# LabGener.net
KiCad netlist of a schematic drawn in Altium Designer
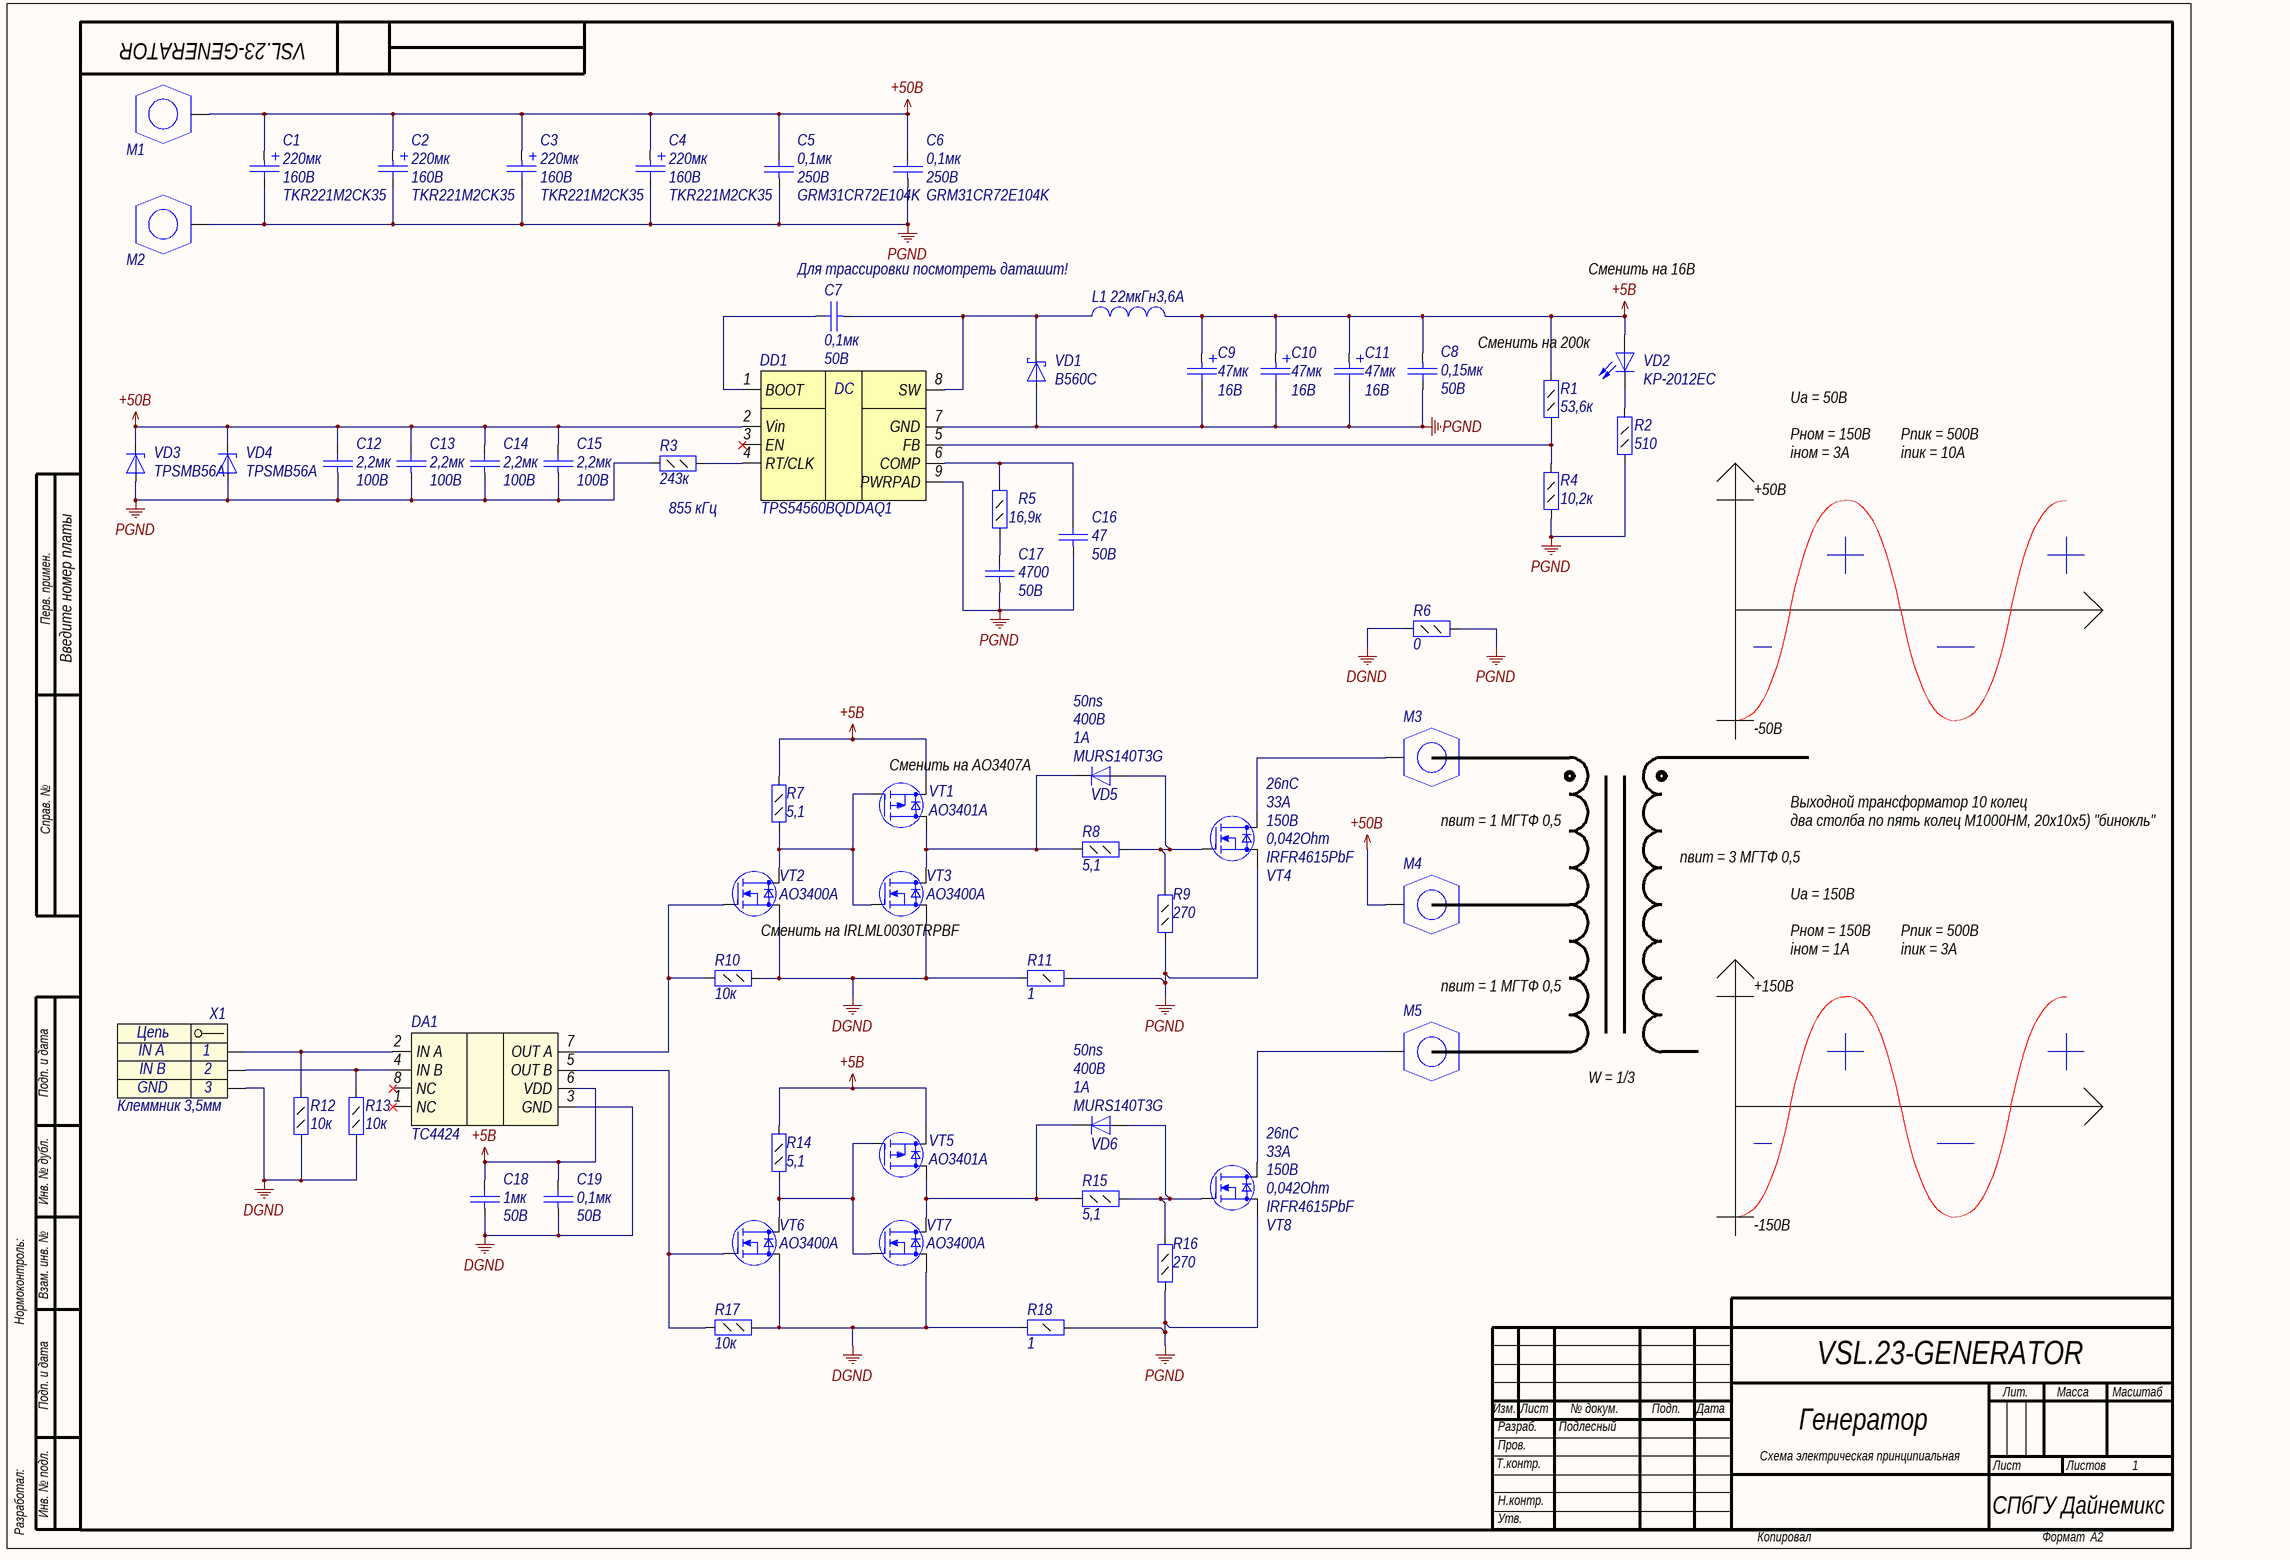
[diagram p0: LabGener.SchDoc]

(export (version "E")
  (design (tool "Eeschema 10.0.6"))
  (components
    (comp (ref "C1")
      (value "220мк")
      (footprint "K50-35(16X35)_V")
      (description "Конденсатор полярный")
      (fields
        (field (name "VOLTAGE") "160B")
        (field (name "PART NUMBER") "TKR221M2CK35")
        (field (name "Comment") "Capacitor_pol")
      )
      (libsource (lib "MOP44") (part "Capacitor_pol"))
    )
    (comp (ref "C2")
      (value "220мк")
      (footprint "K50-35(16X35)_V")
      (description "Конденсатор полярный")
      (fields
        (field (name "VOLTAGE") "160B")
        (field (name "PART NUMBER") "TKR221M2CK35")
        (field (name "Comment") "Capacitor_pol")
      )
      (libsource (lib "MOP44") (part "Capacitor_pol"))
    )
    (comp (ref "C3")
      (value "220мк")
      (footprint "K50-35(16X35)_V")
      (description "Конденсатор полярный")
      (fields
        (field (name "VOLTAGE") "160B")
        (field (name "PART NUMBER") "TKR221M2CK35")
        (field (name "Comment") "Capacitor_pol")
      )
      (libsource (lib "MOP44") (part "Capacitor_pol"))
    )
    (comp (ref "C4")
      (value "220мк")
      (footprint "K50-35(16X35)_V")
      (description "Конденсатор полярный")
      (fields
        (field (name "VOLTAGE") "160B")
        (field (name "PART NUMBER") "TKR221M2CK35")
        (field (name "Comment") "Capacitor_pol")
      )
      (libsource (lib "MOP44") (part "Capacitor_pol"))
    )
    (comp (ref "C5")
      (value "0,1мк")
      (footprint "C1206")
      (description "Конденсатор")
      (fields (field (name "VOLTAGE") "250В") (field (name "PART NUMBER") "GRM31CR72E104K"))
      (libsource (lib "MOP44") (part "Capacitor"))
    )
    (comp (ref "C6")
      (value "0,1мк")
      (footprint "C1206")
      (description "Конденсатор")
      (fields (field (name "VOLTAGE") "250В") (field (name "PART NUMBER") "GRM31CR72E104K"))
      (libsource (lib "MOP44") (part "Capacitor"))
    )
    (comp (ref "C7")
      (value "0,1мк")
      (footprint "C0402")
      (description "Конденсатор")
      (fields (field (name "VOLTAGE") "50В") (field (name "PART NUMBER") "GRM155R71H104KE14D "))
      (libsource (lib "MOP44") (part "Capacitor"))
    )
    (comp (ref "C8")
      (value "0,15мк")
      (footprint "C1812")
      (description "Конденсатор")
      (fields (field (name "VOLTAGE") "50В") (field (name "PART NUMBER") "C4532C0G1H154J250KA "))
      (libsource (lib "MOP44") (part "Capacitor"))
    )
    (comp (ref "C9")
      (value "47мк")
      (footprint "TANTAL CASE C")
      (description "Конденсатор полярный")
      (fields
        (field (name "VOLTAGE") "16В")
        (field (name "PART NUMBER") "TECAP47/16VC10")
        (field (name "Comment") "Capacitor_pol")
      )
      (libsource (lib "MOP44") (part "Capacitor_pol"))
    )
    (comp (ref "C10")
      (value "47мк")
      (footprint "TANTAL CASE C")
      (description "Конденсатор полярный")
      (fields
        (field (name "VOLTAGE") "16В")
        (field (name "PART NUMBER") "TECAP47/16VC10")
        (field (name "Comment") "Capacitor_pol")
      )
      (libsource (lib "MOP44") (part "Capacitor_pol"))
    )
    (comp (ref "C11")
      (value "47мк")
      (footprint "TANTAL CASE C")
      (description "Конденсатор полярный")
      (fields
        (field (name "VOLTAGE") "16В")
        (field (name "PART NUMBER") "TECAP47/16VC10")
        (field (name "Comment") "Capacitor_pol")
      )
      (libsource (lib "MOP44") (part "Capacitor_pol"))
    )
    (comp (ref "C12")
      (value "2,2мк")
      (footprint "C1812")
      (description "Конденсатор")
      (fields (field (name "VOLTAGE") "100В") (field (name "PART NUMBER") "C4532X7R2A225M"))
      (libsource (lib "MOP44") (part "Capacitor"))
    )
    (comp (ref "C13")
      (value "2,2мк")
      (footprint "C1812")
      (description "Конденсатор")
      (fields (field (name "VOLTAGE") "100В") (field (name "PART NUMBER") "C4532X7R2A225M"))
      (libsource (lib "MOP44") (part "Capacitor"))
    )
    (comp (ref "C14")
      (value "2,2мк")
      (footprint "C1812")
      (description "Конденсатор")
      (fields (field (name "VOLTAGE") "100В") (field (name "PART NUMBER") "C4532X7R2A225M"))
      (libsource (lib "MOP44") (part "Capacitor"))
    )
    (comp (ref "C15")
      (value "2,2мк")
      (footprint "C1812")
      (description "Конденсатор")
      (fields (field (name "VOLTAGE") "100В") (field (name "PART NUMBER") "C4532X7R2A225M"))
      (libsource (lib "MOP44") (part "Capacitor"))
    )
    (comp (ref "C16")
      (value "47")
      (footprint "C0805")
      (description "Конденсатор")
      (fields (field (name "VOLTAGE") "50В") (field (name "PART NUMBER") "GRM2165C1H470JD01D"))
      (libsource (lib "MOP44") (part "Capacitor"))
    )
    (comp (ref "C17")
      (value "4700")
      (footprint "C0805")
      (description "Конденсатор")
      (fields (field (name "VOLTAGE") "50В") (field (name "PART NUMBER") "GRM216R71H472K"))
      (libsource (lib "MOP44") (part "Capacitor"))
    )
    (comp (ref "C18")
      (value "1мк")
      (footprint "C0805")
      (description "Конденсатор")
      (fields (field (name "VOLTAGE") "50B") (field (name "PART NUMBER") "GRM21BR71H105K"))
      (libsource (lib "MOP44") (part "Capacitor"))
    )
    (comp (ref "C19")
      (value "0,1мк")
      (footprint "C0805")
      (description "Конденсатор")
      (fields (field (name "VOLTAGE") "50В") (field (name "PART NUMBER") "GRM21BR71H104KA01L "))
      (libsource (lib "MOP44") (part "Capacitor"))
    )
    (comp (ref "DA1")
      (value "TC4424")
      (footprint "DIP8")
      (description "3A Dual High-Speed Power MOSFET Drivers")
      (fields (field (name "PART NUMBER") "TC4424CPA"))
      (libsource (lib "MOP44") (part "TC4424"))
    )
    (comp (ref "DD1")
      (value "TPS54560")
      (footprint "SO Powerpad8")
      (description "5-A, Wide Input Range, Step-Down Converter")
      (fields
        (field (name "PART NUMBER") "TPS54560BQDDAQ1")
        (field (name "MANUFACTURER") "Texas Instruments")
      )
      (libsource (lib "MOP44") (part "TPS54560"))
    )
    (comp (ref "L1")
      (value "22мкГн")
      (footprint "IND_12.5x12.5")
      (description "EMI Suppression Filter")
      (fields
        (field (name "RATED CURRENT") "3,6A")
        (field (name "PART NUMBER") "B82477G4223M000")
        (field (name "Comment") "Inductor")
      )
      (libsource (lib "MOP44") (part "Inductor"))
    )
    (comp (ref "M1") (value "SCREW") (footprint "SCREW2.5") (libsource (lib "MOP44") (part "SCREW")))
    (comp (ref "M2") (value "SCREW") (footprint "SCREW2.5") (libsource (lib "MOP44") (part "SCREW")))
    (comp (ref "M3") (value "SCREW") (footprint "SCREW2.5") (libsource (lib "MOP44") (part "SCREW")))
    (comp (ref "M4") (value "SCREW") (footprint "SCREW2.5") (libsource (lib "MOP44") (part "SCREW")))
    (comp (ref "M5") (value "SCREW") (footprint "SCREW2.5") (libsource (lib "MOP44") (part "SCREW")))
    (comp (ref "R1")
      (value "53,6к")
      (footprint "R0805")
      (description "Резистор")
      (fields (field (name "PART NUMBER") "RC0805FR-0753K6L") (field (name "POWER") "0,125Вт"))
      (libsource (lib "MOP44") (part "Resistor_0,125Вт"))
    )
    (comp (ref "R2")
      (value "510")
      (footprint "R0805")
      (description "Резистор")
      (fields (field (name "PART NUMBER") "RC0805FR-07510RL") (field (name "POWER") "0,125Вт"))
      (libsource (lib "MOP44") (part "Resistor_0,125Вт"))
    )
    (comp (ref "R3")
      (value "243к")
      (footprint "R0805")
      (description "Резистор")
      (fields (field (name "PART NUMBER") "RC0805FR-07243KL") (field (name "POWER") "0,125Вт"))
      (libsource (lib "") (part "Resistor_0,125Вт_2"))
    )
    (comp (ref "R4")
      (value "10,2к")
      (footprint "R0805")
      (description "Резистор")
      (fields (field (name "PART NUMBER") "RC0805FR-0710K2L") (field (name "POWER") "0,125Вт"))
      (libsource (lib "MOP44") (part "Resistor_0,125Вт"))
    )
    (comp (ref "R5")
      (value "16,9к")
      (footprint "R0805")
      (description "Резистор")
      (fields (field (name "PART NUMBER") "RC0805FR-0716K9L") (field (name "POWER") "0,125Вт"))
      (libsource (lib "MOP44") (part "Resistor_0,125Вт"))
    )
    (comp (ref "R6")
      (value "0")
      (footprint "R0805")
      (description "Резистор")
      (fields (field (name "PART NUMBER") "RC0805FR-070RL") (field (name "POWER") "0,125Вт"))
      (libsource (lib "") (part "Resistor_0,125Вт_2"))
    )
    (comp (ref "R7")
      (value "5,1")
      (footprint "R0805")
      (description "Резистор")
      (fields (field (name "PART NUMBER") "RC0805FR-075R1L") (field (name "POWER") "0,125Вт"))
      (libsource (lib "MOP44") (part "Resistor_0,125Вт"))
    )
    (comp (ref "R8")
      (value "5,1")
      (footprint "R0805")
      (description "Резистор")
      (fields (field (name "PART NUMBER") "RC0805FR-075R1L") (field (name "POWER") "0,125Вт"))
      (libsource (lib "") (part "Resistor_0,125Вт_2"))
    )
    (comp (ref "R9")
      (value "270")
      (footprint "R0805")
      (description "Резистор")
      (fields (field (name "PART NUMBER") "RC0805FR-07270RL") (field (name "POWER") "0,125Вт"))
      (libsource (lib "MOP44") (part "Resistor_0,125Вт"))
    )
    (comp (ref "R10")
      (value "10к")
      (footprint "R0805")
      (description "Резистор")
      (fields (field (name "PART NUMBER") "RC0805FR-0710KL") (field (name "POWER") "0,125Вт"))
      (libsource (lib "") (part "Resistor_0,125Вт_1"))
    )
    (comp (ref "R11")
      (value "1")
      (footprint "R1206")
      (description "Резистор")
      (fields (field (name "PART NUMBER") "RC1206FR-071RL") (field (name "POWER") "0,25Вт"))
      (libsource (lib "MOP44") (part "Resistor_0,25Вт"))
    )
    (comp (ref "R12")
      (value "10к")
      (footprint "R0805")
      (description "Резистор")
      (fields (field (name "PART NUMBER") "RC0805FR-0710KL") (field (name "POWER") "0,125Вт"))
      (libsource (lib "MOP44") (part "Resistor_0,125Вт"))
    )
    (comp (ref "R13")
      (value "10к")
      (footprint "R0805")
      (description "Резистор")
      (fields (field (name "PART NUMBER") "RC0805FR-0710KL") (field (name "POWER") "0,125Вт"))
      (libsource (lib "MOP44") (part "Resistor_0,125Вт"))
    )
    (comp (ref "R14")
      (value "5,1")
      (footprint "R0805")
      (description "Резистор")
      (fields (field (name "PART NUMBER") "RC0805FR-075R1L") (field (name "POWER") "0,125Вт"))
      (libsource (lib "MOP44") (part "Resistor_0,125Вт"))
    )
    (comp (ref "R15")
      (value "5,1")
      (footprint "R0805")
      (description "Резистор")
      (fields (field (name "PART NUMBER") "RC0805FR-075R1L") (field (name "POWER") "0,125Вт"))
      (libsource (lib "") (part "Resistor_0,125Вт_2"))
    )
    (comp (ref "R16")
      (value "270")
      (footprint "R0805")
      (description "Резистор")
      (fields (field (name "PART NUMBER") "RC0805FR-07270RL") (field (name "POWER") "0,125Вт"))
      (libsource (lib "MOP44") (part "Resistor_0,125Вт"))
    )
    (comp (ref "R17")
      (value "10к")
      (footprint "R0805")
      (description "Резистор")
      (fields (field (name "PART NUMBER") "RC0805FR-0710KL") (field (name "POWER") "0,125Вт"))
      (libsource (lib "") (part "Resistor_0,125Вт_1"))
    )
    (comp (ref "R18")
      (value "1")
      (footprint "R1206")
      (description "Резистор")
      (fields (field (name "PART NUMBER") "RC1206FR-071RL") (field (name "POWER") "0,25Вт"))
      (libsource (lib "MOP44") (part "Resistor_0,25Вт"))
    )
    (comp (ref "VD1")
      (value "DiodeSchottky")
      (footprint "SMC")
      (description "Диод Шоттки")
      (fields (field (name "PART NUMBER") "B560C"))
      (libsource (lib "MOP44") (part "DiodeSchottky"))
    )
    (comp (ref "VD2")
      (value "LED")
      (footprint "L_0805")
      (description "Светодиод")
      (fields (field (name "PART NUMBER") "KP-2012EC"))
      (libsource (lib "MOP44") (part "LED"))
    )
    (comp (ref "VD3")
      (value "DiodeZener")
      (footprint "SMB")
      (description "Cтабилитрон (лавинный выпрямительный диод) односторонний")
      (fields (field (name "PART NUMBER") "TPSMB56A"))
      (libsource (lib "MOP44") (part "DiodeZener"))
    )
    (comp (ref "VD4")
      (value "DiodeZener")
      (footprint "SMB")
      (description "Cтабилитрон (лавинный выпрямительный диод) односторонний")
      (fields (field (name "PART NUMBER") "TPSMB56A"))
      (libsource (lib "MOP44") (part "DiodeZener"))
    )
    (comp (ref "VD5")
      (value "Diode")
      (footprint "SMB")
      (description "Диод")
      (fields
        (field (name "FORWARD CURRENT") "1A")
        (field (name "BREAKDOWN VOLTAGE") "400B")
        (field (name "REVERSE RECOVERY TIME") "50ns")
        (field (name "PART NUMBER") "MURS140T3G")
      )
      (libsource (lib "MOP44") (part "Diode"))
    )
    (comp (ref "VD6")
      (value "Diode")
      (footprint "SMB")
      (description "Диод")
      (fields
        (field (name "FORWARD CURRENT") "1A")
        (field (name "BREAKDOWN VOLTAGE") "400B")
        (field (name "REVERSE RECOVERY TIME") "50ns")
        (field (name "PART NUMBER") "MURS140T3G")
      )
      (libsource (lib "MOP44") (part "Diode"))
    )
    (comp (ref "VT1")
      (value "P-MOSFET")
      (footprint "SOT23-3")
      (description "N-MOSFET")
      (fields (field (name "PART NUMBER") "AO3401A") (field (name "MANUFACTURER") "Alpha&Omega"))
      (libsource (lib "MOP44") (part "P-MOSFET"))
    )
    (comp (ref "VT2")
      (value "N-MOSFET")
      (footprint "SOT23-3")
      (fields (field (name "PART NUMBER") "AO3400A") (field (name "MANUFACTURER") "Alpha&Omega"))
      (libsource (lib "MOP44") (part "N-MOSFET"))
    )
    (comp (ref "VT3")
      (value "N-MOSFET")
      (footprint "SOT23-3")
      (fields (field (name "PART NUMBER") "AO3400A") (field (name "MANUFACTURER") "Alpha&Omega"))
      (libsource (lib "MOP44") (part "N-MOSFET"))
    )
    (comp (ref "VT4")
      (value "N-MOSFET")
      (footprint "DPAK")
      (fields
        (field (name "V DRAIN-SOURCE MAX") "150B")
        (field (name "RDS") "0,042Ohm")
        (field (name "CONTINUOUS DRAIN CURRENT") "33A")
        (field (name "TOTAL GATE CHARGE") "26nC")
        (field (name "PART NUMBER") "IRFR4615PbF")
        (field (name "MANUFACTURER") "International Rectifier")
      )
      (libsource (lib "MOP44") (part "N-MOSFET"))
    )
    (comp (ref "VT5")
      (value "P-MOSFET")
      (footprint "SOT23-3")
      (description "N-MOSFET")
      (fields (field (name "PART NUMBER") "AO3401A") (field (name "MANUFACTURER") "Alpha&Omega"))
      (libsource (lib "MOP44") (part "P-MOSFET"))
    )
    (comp (ref "VT6")
      (value "N-MOSFET")
      (footprint "SOT23-3")
      (fields (field (name "PART NUMBER") "AO3400A") (field (name "MANUFACTURER") "Alpha&Omega"))
      (libsource (lib "MOP44") (part "N-MOSFET"))
    )
    (comp (ref "VT7")
      (value "N-MOSFET")
      (footprint "SOT23-3")
      (fields (field (name "PART NUMBER") "AO3400A") (field (name "MANUFACTURER") "Alpha&Omega"))
      (libsource (lib "MOP44") (part "N-MOSFET"))
    )
    (comp (ref "VT8")
      (value "N-MOSFET")
      (footprint "DPAK")
      (fields
        (field (name "V DRAIN-SOURCE MAX") "150B")
        (field (name "RDS") "0,042Ohm")
        (field (name "CONTINUOUS DRAIN CURRENT") "33A")
        (field (name "TOTAL GATE CHARGE") "26nC")
        (field (name "PART NUMBER") "IRFR4615PbF")
        (field (name "MANUFACTURER") "International Rectifier")
      )
      (libsource (lib "MOP44") (part "N-MOSFET"))
    )
    (comp (ref "X1")
      (value "Клеммник 3,5мм")
      (footprint "TERMINAL-3WAY-3.5MM")
      (description "Разъем - 3 конт. клеммник")
      (libsource (lib "MOP44") (part "Header_3_trm"))
    )
  )
  (nets
    (net (code "1") (name "+5B") (class "Default")
      (node (ref "C10") (pin "1") (pinfunction "1_1") (pintype "passive"))
      (node (ref "C11") (pin "1") (pinfunction "1_1") (pintype "passive"))
      (node (ref "C18") (pin "2") (pinfunction "2_2") (pintype "passive"))
      (node (ref "C19") (pin "2") (pinfunction "2_2") (pintype "passive"))
      (node (ref "C8") (pin "1") (pinfunction "1_1") (pintype "passive"))
      (node (ref "C9") (pin "1") (pinfunction "1_1") (pintype "passive"))
      (node (ref "DA1") (pin "6") (pinfunction "VDD_6") (pintype "passive"))
      (node (ref "L1") (pin "2") (pinfunction "2_2") (pintype "passive"))
      (node (ref "R1") (pin "2") (pinfunction "2_2") (pintype "passive"))
      (node (ref "R14") (pin "2") (pinfunction "2_2") (pintype "passive"))
      (node (ref "R7") (pin "2") (pinfunction "2_2") (pintype "passive"))
      (node (ref "VD2") (pin "2") (pinfunction "A_2") (pintype "passive"))
      (node (ref "VT1") (pin "3") (pinfunction "S_3") (pintype "passive"))
      (node (ref "VT5") (pin "3") (pinfunction "S_3") (pintype "passive"))
    )
    (net (code "2") (name "+50B") (class "Default")
      (node (ref "C1") (pin "1") (pinfunction "1_1") (pintype "passive"))
      (node (ref "C12") (pin "2") (pinfunction "2_2") (pintype "passive"))
      (node (ref "C13") (pin "2") (pinfunction "2_2") (pintype "passive"))
      (node (ref "C14") (pin "2") (pinfunction "2_2") (pintype "passive"))
      (node (ref "C15") (pin "2") (pinfunction "2_2") (pintype "passive"))
      (node (ref "C2") (pin "1") (pinfunction "1_1") (pintype "passive"))
      (node (ref "C3") (pin "1") (pinfunction "1_1") (pintype "passive"))
      (node (ref "C4") (pin "1") (pinfunction "1_1") (pintype "passive"))
      (node (ref "C5") (pin "2") (pinfunction "2_2") (pintype "passive"))
      (node (ref "C6") (pin "2") (pinfunction "2_2") (pintype "passive"))
      (node (ref "DD1") (pin "2") (pinfunction "Vin_2") (pintype "passive"))
      (node (ref "M1") (pin "1") (pinfunction "1_1") (pintype "passive"))
      (node (ref "M4") (pin "1") (pinfunction "1_1") (pintype "passive"))
      (node (ref "VD3") (pin "1") (pinfunction "K_1") (pintype "passive"))
      (node (ref "VD4") (pin "1") (pinfunction "K_1") (pintype "passive"))
    )
    (net (code "3") (name "DGND") (class "Default")
      (node (ref "C18") (pin "1") (pinfunction "1_1") (pintype "passive"))
      (node (ref "C19") (pin "1") (pinfunction "1_1") (pintype "passive"))
      (node (ref "DA1") (pin "3") (pinfunction "GND_3") (pintype "passive"))
      (node (ref "R10") (pin "1") (pinfunction "1_1") (pintype "passive"))
      (node (ref "R11") (pin "1") (pinfunction "1_1") (pintype "passive"))
      (node (ref "R12") (pin "1") (pinfunction "1_1") (pintype "passive"))
      (node (ref "R13") (pin "1") (pinfunction "1_1") (pintype "passive"))
      (node (ref "R17") (pin "1") (pinfunction "1_1") (pintype "passive"))
      (node (ref "R18") (pin "1") (pinfunction "1_1") (pintype "passive"))
      (node (ref "R6") (pin "1") (pinfunction "1_1") (pintype "passive"))
      (node (ref "VT2") (pin "3") (pinfunction "S_3") (pintype "passive"))
      (node (ref "VT3") (pin "3") (pinfunction "S_3") (pintype "passive"))
      (node (ref "VT6") (pin "3") (pinfunction "S_3") (pintype "passive"))
      (node (ref "VT7") (pin "3") (pinfunction "S_3") (pintype "passive"))
      (node (ref "X1") (pin "3") (pinfunction "3_3") (pintype "passive"))
    )
    (net (code "4") (name "Net-(C17-Pad2)") (class "Default")
      (node (ref "C17") (pin "2") (pinfunction "2_2") (pintype "passive"))
      (node (ref "R5") (pin "1") (pinfunction "1_1") (pintype "passive"))
    )
    (net (code "5") (name "Net-(DA1-IN_A)") (class "Default")
      (node (ref "DA1") (pin "2") (pinfunction "IN_A_2") (pintype "passive"))
      (node (ref "R12") (pin "2") (pinfunction "2_2") (pintype "passive"))
      (node (ref "X1") (pin "1") (pinfunction "1_1") (pintype "passive"))
    )
    (net (code "6") (name "Net-(DA1-IN_B)") (class "Default")
      (node (ref "DA1") (pin "4") (pinfunction "IN_B_4") (pintype "passive"))
      (node (ref "R13") (pin "2") (pinfunction "2_2") (pintype "passive"))
      (node (ref "X1") (pin "2") (pinfunction "2_2") (pintype "passive"))
    )
    (net (code "7") (name "Net-(DA1-OUT_A)") (class "Default")
      (node (ref "DA1") (pin "7") (pinfunction "OUT_A_7") (pintype "passive"))
      (node (ref "R10") (pin "2") (pinfunction "2_2") (pintype "passive"))
      (node (ref "VT2") (pin "1") (pinfunction "G_1") (pintype "passive"))
    )
    (net (code "8") (name "Net-(DA1-OUT_B)") (class "Default")
      (node (ref "DA1") (pin "5") (pinfunction "OUT_B_5") (pintype "passive"))
      (node (ref "R17") (pin "2") (pinfunction "2_2") (pintype "passive"))
      (node (ref "VT6") (pin "1") (pinfunction "G_1") (pintype "passive"))
    )
    (net (code "9") (name "Net-(DD1-BOOT)") (class "Default")
      (node (ref "C7") (pin "2") (pinfunction "2_2") (pintype "passive"))
      (node (ref "DD1") (pin "1") (pinfunction "BOOT_1") (pintype "passive"))
    )
    (net (code "10") (name "Net-(DD1-COMP)") (class "Default")
      (node (ref "C16") (pin "2") (pinfunction "2_2") (pintype "passive"))
      (node (ref "DD1") (pin "6") (pinfunction "COMP_6") (pintype "passive"))
      (node (ref "R5") (pin "2") (pinfunction "2_2") (pintype "passive"))
    )
    (net (code "11") (name "Net-(DD1-FB)") (class "Default")
      (node (ref "DD1") (pin "5") (pinfunction "FB_5") (pintype "passive"))
      (node (ref "R1") (pin "1") (pinfunction "1_1") (pintype "passive"))
      (node (ref "R4") (pin "2") (pinfunction "2_2") (pintype "passive"))
    )
    (net (code "12") (name "Net-(DD1-RT{slash}CLK)") (class "Default")
      (node (ref "DD1") (pin "4") (pinfunction "RT/CLK_4") (pintype "passive"))
      (node (ref "R3") (pin "2") (pinfunction "2_2") (pintype "passive"))
    )
    (net (code "13") (name "Net-(DD1-SW)") (class "Default")
      (node (ref "C7") (pin "1") (pinfunction "1_1") (pintype "passive"))
      (node (ref "DD1") (pin "8") (pinfunction "SW_8") (pintype "passive"))
      (node (ref "L1") (pin "1") (pinfunction "1_1") (pintype "passive"))
      (node (ref "VD1") (pin "1") (pinfunction "K_1") (pintype "passive"))
    )
    (net (code "14") (name "Net-(VD2-K)") (class "Default")
      (node (ref "R2") (pin "2") (pinfunction "2_2") (pintype "passive"))
      (node (ref "VD2") (pin "1") (pinfunction "K_1") (pintype "passive"))
    )
    (net (code "15") (name "Net-(VD5-A)") (class "Default")
      (node (ref "R8") (pin "2") (pinfunction "2_2") (pintype "passive"))
      (node (ref "R9") (pin "2") (pinfunction "2_2") (pintype "passive"))
      (node (ref "VD5") (pin "2") (pinfunction "A_2") (pintype "passive"))
      (node (ref "VT4") (pin "1") (pinfunction "G_1") (pintype "passive"))
    )
    (net (code "16") (name "Net-(VD5-K)") (class "Default")
      (node (ref "R8") (pin "1") (pinfunction "1_1") (pintype "passive"))
      (node (ref "VD5") (pin "1") (pinfunction "K_1") (pintype "passive"))
      (node (ref "VT1") (pin "2") (pinfunction "D_2") (pintype "passive"))
      (node (ref "VT3") (pin "2") (pinfunction "D_2") (pintype "passive"))
    )
    (net (code "17") (name "Net-(VD6-A)") (class "Default")
      (node (ref "R15") (pin "2") (pinfunction "2_2") (pintype "passive"))
      (node (ref "R16") (pin "2") (pinfunction "2_2") (pintype "passive"))
      (node (ref "VD6") (pin "2") (pinfunction "A_2") (pintype "passive"))
      (node (ref "VT8") (pin "1") (pinfunction "G_1") (pintype "passive"))
    )
    (net (code "18") (name "Net-(VD6-K)") (class "Default")
      (node (ref "R15") (pin "1") (pinfunction "1_1") (pintype "passive"))
      (node (ref "VD6") (pin "1") (pinfunction "K_1") (pintype "passive"))
      (node (ref "VT5") (pin "2") (pinfunction "D_2") (pintype "passive"))
      (node (ref "VT7") (pin "2") (pinfunction "D_2") (pintype "passive"))
    )
    (net (code "19") (name "Net-(VT1-G)") (class "Default")
      (node (ref "R7") (pin "1") (pinfunction "1_1") (pintype "passive"))
      (node (ref "VT1") (pin "1") (pinfunction "G_1") (pintype "passive"))
      (node (ref "VT2") (pin "2") (pinfunction "D_2") (pintype "passive"))
      (node (ref "VT3") (pin "1") (pinfunction "G_1") (pintype "passive"))
    )
    (net (code "20") (name "Net-(VT4-D)") (class "Default")
      (node (ref "M3") (pin "1") (pinfunction "1_1") (pintype "passive"))
      (node (ref "VT4") (pin "2") (pinfunction "D_2") (pintype "passive"))
    )
    (net (code "21") (name "Net-(VT5-G)") (class "Default")
      (node (ref "R14") (pin "1") (pinfunction "1_1") (pintype "passive"))
      (node (ref "VT5") (pin "1") (pinfunction "G_1") (pintype "passive"))
      (node (ref "VT6") (pin "2") (pinfunction "D_2") (pintype "passive"))
      (node (ref "VT7") (pin "1") (pinfunction "G_1") (pintype "passive"))
    )
    (net (code "22") (name "Net-(VT8-D)") (class "Default")
      (node (ref "M5") (pin "1") (pinfunction "1_1") (pintype "passive"))
      (node (ref "VT8") (pin "2") (pinfunction "D_2") (pintype "passive"))
    )
    (net (code "23") (name "PGND") (class "Default")
      (node (ref "C1") (pin "2") (pinfunction "2_2") (pintype "passive"))
      (node (ref "C10") (pin "2") (pinfunction "2_2") (pintype "passive"))
      (node (ref "C11") (pin "2") (pinfunction "2_2") (pintype "passive"))
      (node (ref "C12") (pin "1") (pinfunction "1_1") (pintype "passive"))
      (node (ref "C13") (pin "1") (pinfunction "1_1") (pintype "passive"))
      (node (ref "C14") (pin "1") (pinfunction "1_1") (pintype "passive"))
      (node (ref "C15") (pin "1") (pinfunction "1_1") (pintype "passive"))
      (node (ref "C16") (pin "1") (pinfunction "1_1") (pintype "passive"))
      (node (ref "C17") (pin "1") (pinfunction "1_1") (pintype "passive"))
      (node (ref "C2") (pin "2") (pinfunction "2_2") (pintype "passive"))
      (node (ref "C3") (pin "2") (pinfunction "2_2") (pintype "passive"))
      (node (ref "C4") (pin "2") (pinfunction "2_2") (pintype "passive"))
      (node (ref "C5") (pin "1") (pinfunction "1_1") (pintype "passive"))
      (node (ref "C6") (pin "1") (pinfunction "1_1") (pintype "passive"))
      (node (ref "C8") (pin "2") (pinfunction "2_2") (pintype "passive"))
      (node (ref "C9") (pin "2") (pinfunction "2_2") (pintype "passive"))
      (node (ref "DD1") (pin "7") (pinfunction "GND_7") (pintype "passive"))
      (node (ref "DD1") (pin "9") (pinfunction "PWRPAD_9") (pintype "passive"))
      (node (ref "M2") (pin "1") (pinfunction "1_1") (pintype "passive"))
      (node (ref "R11") (pin "2") (pinfunction "2_2") (pintype "passive"))
      (node (ref "R16") (pin "1") (pinfunction "1_1") (pintype "passive"))
      (node (ref "R18") (pin "2") (pinfunction "2_2") (pintype "passive"))
      (node (ref "R2") (pin "1") (pinfunction "1_1") (pintype "passive"))
      (node (ref "R3") (pin "1") (pinfunction "1_1") (pintype "passive"))
      (node (ref "R4") (pin "1") (pinfunction "1_1") (pintype "passive"))
      (node (ref "R6") (pin "2") (pinfunction "2_2") (pintype "passive"))
      (node (ref "R9") (pin "1") (pinfunction "1_1") (pintype "passive"))
      (node (ref "VD1") (pin "2") (pinfunction "A_2") (pintype "passive"))
      (node (ref "VD3") (pin "2") (pinfunction "A_2") (pintype "passive"))
      (node (ref "VD4") (pin "2") (pinfunction "A_2") (pintype "passive"))
      (node (ref "VT4") (pin "3") (pinfunction "S_3") (pintype "passive"))
      (node (ref "VT8") (pin "3") (pinfunction "S_3") (pintype "passive"))
    )
    (net (code "24") (name "unconnected-(DA1-NC-Pad1)") (class "Default")
      (node (ref "DA1") (pin "1") (pinfunction "NC_1") (pintype "passive+no_connect"))
    )
    (net (code "25") (name "unconnected-(DA1-NC-Pad8)") (class "Default")
      (node (ref "DA1") (pin "8") (pinfunction "NC_8") (pintype "passive+no_connect"))
    )
    (net (code "26") (name "unconnected-(DD1-EN-Pad3)") (class "Default")
      (node (ref "DD1") (pin "3") (pinfunction "EN_3") (pintype "passive+no_connect"))
    )
  )
)
